# LTC1569.net
KiCad netlist of a schematic drawn in EasyEDA Pro
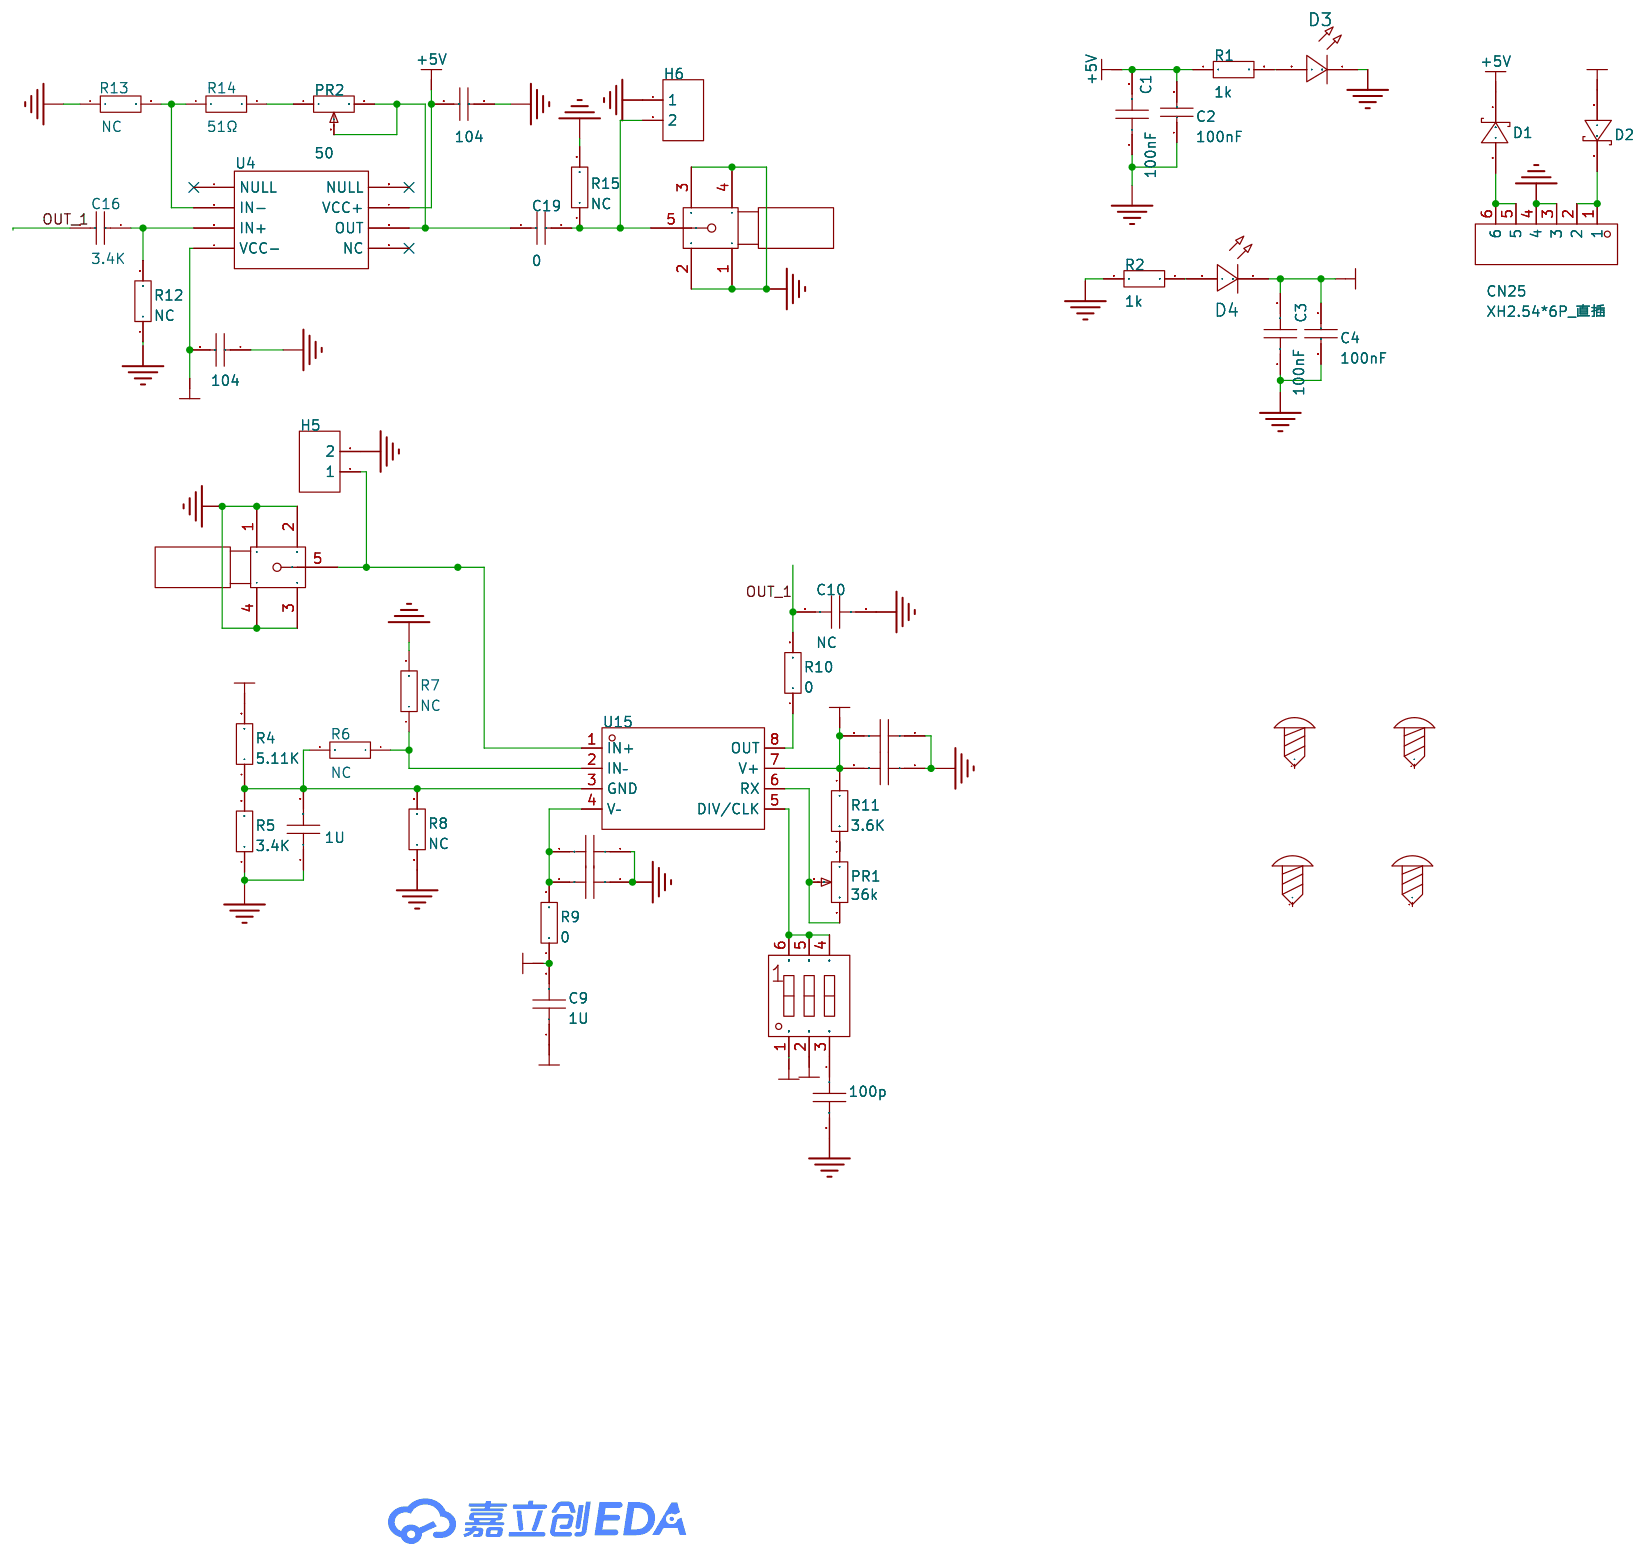
[diagram p0: schematic sheet]

(export (version "E")
  (design (tool "Eeschema 10.0.6"))
  (components
    (comp (ref "C1")
      (value "100nF")
      (footprint "easyedapro:C0805")
      (libsource (lib "easyedapro") (part "CapAcitance"))
    )
    (comp (ref "C2")
      (value "100nF")
      (footprint "easyedapro:C1210")
      (description "容值:10uF;精度:±10%;额定电压:25V;材质(温度系数):X7R;")
      (fields
        (field (name "Manufacturer Part") "CL32B106KAJNNNE")
        (field (name "Manufacturer") "SAMSUNG(三星)")
      )
      (libsource (lib "easyedapro") (part "CL32B106KAJNNNE"))
    )
    (comp (ref "C3")
      (value "100nF")
      (footprint "easyedapro:C0805")
      (libsource (lib "easyedapro") (part "CapAcitance"))
    )
    (comp (ref "C4")
      (value "100nF")
      (footprint "easyedapro:C1210")
      (description "容值:10uF;精度:±10%;额定电压:25V;材质(温度系数):X7R;")
      (fields
        (field (name "Manufacturer Part") "CL32B106KAJNNNE")
        (field (name "Manufacturer") "SAMSUNG(三星)")
      )
      (libsource (lib "easyedapro") (part "CL32B106KAJNNNE"))
    )
    (comp (ref "C6")
      (value "1U")
      (footprint "easyedapro:C0805")
      (libsource (lib "easyedapro") (part "CapAcitance"))
    )
    (comp (ref "C7")
      (value "100nF")
      (footprint "easyedapro:C0805")
      (libsource (lib "easyedapro") (part "CapAcitance"))
    )
    (comp (ref "C8")
      (value "100nF")
      (footprint "easyedapro:C0805")
      (libsource (lib "easyedapro") (part "CapAcitance"))
    )
    (comp (ref "C9")
      (value "1U")
      (footprint "easyedapro:C0805")
      (libsource (lib "easyedapro") (part "CapAcitance"))
    )
    (comp (ref "C10")
      (value "NC")
      (footprint "easyedapro:C0805")
      (libsource (lib "easyedapro") (part "CapAcitance"))
    )
    (comp (ref "C11")
      (value "100nF")
      (footprint "easyedapro:C0805")
      (libsource (lib "easyedapro") (part "CapAcitance"))
    )
    (comp (ref "C12")
      (value "100nF")
      (footprint "easyedapro:C0805")
      (libsource (lib "easyedapro") (part "CapAcitance"))
    )
    (comp (ref "C14")
      (value "100p")
      (footprint "easyedapro:C0805")
      (libsource (lib "easyedapro") (part "CapAcitance"))
    )
    (comp (ref "C16")
      (value "3.4K")
      (footprint "easyedapro:C0805")
      (description "容值:100pF;精度:±5%;额定电压:50V;材质(温度系数):C0G;")
      (fields
        (field (name "Manufacturer Part") "CL21C101JBANNNC")
        (field (name "Manufacturer") "SAMSUNG(三星)")
      )
      (libsource (lib "easyedapro") (part "CL21C101JBANNNC"))
    )
    (comp (ref "C17")
      (value "104")
      (footprint "easyedapro:C0805")
      (description "容值:100pF;精度:±5%;额定电压:50V;材质(温度系数):C0G;")
      (fields
        (field (name "Manufacturer Part") "CL21C101JBANNNC")
        (field (name "Manufacturer") "SAMSUNG(三星)")
      )
      (libsource (lib "easyedapro") (part "CL21C101JBANNNC"))
    )
    (comp (ref "C18")
      (value "104")
      (footprint "easyedapro:C0805")
      (description "容值:100pF;精度:±5%;额定电压:50V;材质(温度系数):C0G;")
      (fields
        (field (name "Manufacturer Part") "CL21C101JBANNNC")
        (field (name "Manufacturer") "SAMSUNG(三星)")
      )
      (libsource (lib "easyedapro") (part "CL21C101JBANNNC"))
    )
    (comp (ref "C19")
      (value "0")
      (footprint "easyedapro:C0805")
      (description "容值:100pF;精度:±5%;额定电压:50V;材质(温度系数):C0G;")
      (fields
        (field (name "Manufacturer Part") "CL21C101JBANNNC")
        (field (name "Manufacturer") "SAMSUNG(三星)")
      )
      (libsource (lib "easyedapro") (part "CL21C101JBANNNC"))
    )
    (comp (ref "CN25")
      (value "XH2.54*6P_直插")
      (footprint "easyedapro:CONN-TH_XH2.54-6P")
      (libsource (lib "easyedapro") (part "XH2.54*6P_直插"))
    )
    (comp (ref "D1")
      (value "SD103AWS")
      (footprint "easyedapro:SOD-323_L1.8-W1.3-LS2.5-RD")
      (description "正向压降(Vf):600mV@200mA;直流反向耐压(Vr):40V;整流电流:350mA;")
      (fields (field (name "Manufacturer") "Hottech(合科泰)"))
      (libsource (lib "easyedapro") (part "SD103AWS_C181207"))
    )
    (comp (ref "D2")
      (value "SD103AWS")
      (footprint "easyedapro:SOD-323_L1.8-W1.3-LS2.5-RD")
      (description "正向压降(Vf):600mV@200mA;直流反向耐压(Vr):40V;整流电流:350mA;")
      (fields (field (name "Manufacturer") "Hottech(合科泰)"))
      (libsource (lib "easyedapro") (part "SD103AWS_C181207"))
    )
    (comp (ref "D3")
      (value "~")
      (footprint "easyedapro:LED_0805")
      (libsource (lib "easyedapro") (part "LED_R"))
    )
    (comp (ref "D4")
      (value "~")
      (footprint "easyedapro:LED_0805")
      (libsource (lib "easyedapro") (part "LED_R"))
    )
    (comp (ref "H5")
      (value "~")
      (footprint "easyedapro:HDR-TH_2P-P2.54-V-F")
      (libsource (lib "easyedapro") (part "Header-Female-2.54_1x2"))
    )
    (comp (ref "H6")
      (value "~")
      (footprint "easyedapro:HDR-TH_2P-P2.54-V-F")
      (libsource (lib "easyedapro") (part "Header-Female-2.54_1x2"))
    )
    (comp (ref "PR1")
      (value "36k")
      (footprint "easyedapro:R_3296")
      (libsource (lib "easyedapro") (part "R_3296"))
    )
    (comp (ref "PR2")
      (value "50")
      (footprint "easyedapro:R_3296")
      (libsource (lib "easyedapro") (part "R_3296"))
    )
    (comp (ref "R1") (value "1k") (footprint "easyedapro:R0805") (libsource (lib "easyedapro") (part "电阻")))
    (comp (ref "R2") (value "1k") (footprint "easyedapro:R0805") (libsource (lib "easyedapro") (part "电阻")))
    (comp (ref "R4")
      (value "5.11K")
      (footprint "easyedapro:R0805")
      (libsource (lib "easyedapro") (part "电阻"))
    )
    (comp (ref "R5") (value "3.4K") (footprint "easyedapro:R0805") (libsource (lib "easyedapro") (part "电阻")))
    (comp (ref "R6") (value "NC") (footprint "easyedapro:R0805") (libsource (lib "easyedapro") (part "电阻")))
    (comp (ref "R7") (value "NC") (footprint "easyedapro:R0805") (libsource (lib "easyedapro") (part "电阻")))
    (comp (ref "R8") (value "NC") (footprint "easyedapro:R0805") (libsource (lib "easyedapro") (part "电阻")))
    (comp (ref "R9") (value "0") (footprint "easyedapro:R0805") (libsource (lib "easyedapro") (part "电阻")))
    (comp (ref "R10") (value "0") (footprint "easyedapro:R0805") (libsource (lib "easyedapro") (part "电阻")))
    (comp (ref "R11")
      (value "3.6K")
      (footprint "easyedapro:R0805")
      (libsource (lib "easyedapro") (part "电阻"))
    )
    (comp (ref "R12")
      (value "NC")
      (footprint "easyedapro:R0805")
      (description "电阻类型:厚膜电阻;阻值:51Ω;精度:±1%;功率:125mW;最大工作电压:150V;温度系数:±100ppm/°C;")
      (fields
        (field (name "Manufacturer Part") "0805W8F510JT5E")
        (field (name "Manufacturer") "UNI-ROYAL(厚声)")
      )
      (libsource (lib "easyedapro") (part "0805W8F510JT5E"))
    )
    (comp (ref "R13")
      (value "NC")
      (footprint "easyedapro:R0805")
      (description "电阻类型:厚膜电阻;阻值:51Ω;精度:±1%;功率:125mW;最大工作电压:150V;温度系数:±100ppm/°C;")
      (fields
        (field (name "Manufacturer Part") "0805W8F510JT5E")
        (field (name "Manufacturer") "UNI-ROYAL(厚声)")
      )
      (libsource (lib "easyedapro") (part "0805W8F510JT5E"))
    )
    (comp (ref "R14")
      (value "51Ω")
      (footprint "easyedapro:R0805")
      (description "电阻类型:厚膜电阻;阻值:511Ω;精度:±1%;功率:125mW;最大工作电压:150V;温度系数:±100ppm/°C;")
      (fields
        (field (name "Manufacturer Part") "0805W8F5110T5E")
        (field (name "Manufacturer") "UNI-ROYAL(厚声)")
      )
      (libsource (lib "easyedapro") (part "0805W8F5110T5E"))
    )
    (comp (ref "R15")
      (value "NC")
      (footprint "easyedapro:R0805")
      (description "电阻类型:厚膜电阻;阻值:51Ω;精度:±1%;功率:125mW;最大工作电压:150V;温度系数:±100ppm/°C;")
      (fields
        (field (name "Manufacturer Part") "0805W8F510JT5E")
        (field (name "Manufacturer") "UNI-ROYAL(厚声)")
      )
      (libsource (lib "easyedapro") (part "0805W8F510JT5E"))
    )
    (comp (ref "SCREW9")
      (value "~")
      (footprint "easyedapro:M3螺丝")
      (libsource (lib "easyedapro") (part "螺丝孔"))
    )
    (comp (ref "SCREW10")
      (value "~")
      (footprint "easyedapro:M3螺丝")
      (libsource (lib "easyedapro") (part "螺丝孔"))
    )
    (comp (ref "SCREW11")
      (value "~")
      (footprint "easyedapro:M3螺丝")
      (libsource (lib "easyedapro") (part "螺丝孔"))
    )
    (comp (ref "SCREW12")
      (value "~")
      (footprint "easyedapro:M3螺丝")
      (libsource (lib "easyedapro") (part "螺丝孔"))
    )
    (comp (ref "SW1")
      (value "DSIC03LS-P")
      (footprint "easyedapro:SW-SMD_6P-L8.6-W6.2-P2.54-LS9.8")
      (description "类型:平拨,凸起式;电路结构:单刀单掷;开关位数:3位;额定电流:25mA;额定电压:24V;使用寿命:3千次;颜色:黑色;")
      (fields (field (name "Manufacturer") "XKB Connectivity(中国星坤)"))
      (libsource (lib "easyedapro") (part "DSIC03LS-P"))
    )
    (comp (ref "U4")
      (value "~")
      (footprint "easyedapro:THS4001CD")
      (libsource (lib "easyedapro") (part "THS4001CD"))
    )
    (comp (ref "U15")
      (value "LTC1569IS8-6#TRPBF")
      (footprint "easyedapro:SO-8_L4.9-W3.9-P1.27-LS6.0-BL")
      (description "滤波器阶数:10;滤波器数:1;")
      (fields (field (name "Manufacturer") "ADI(亚德诺)"))
      (libsource (lib "easyedapro") (part "LTC1569IS8-6#TRPBF"))
    )
    (comp (ref "U16") (value "~") (footprint "easyedapro:SMA") (libsource (lib "easyedapro") (part "SMA")))
    (comp (ref "U17") (value "~") (footprint "easyedapro:SMA") (libsource (lib "easyedapro") (part "SMA")))
  )
  (nets
    (net (code "1") (name "+5V") (class "Default")
      (node (ref "C1") (pin "2") (pinfunction "2_2") (pintype "input"))
      (node (ref "C11") (pin "2") (pinfunction "2_2") (pintype "input"))
      (node (ref "C12") (pin "2") (pinfunction "2_2") (pintype "input"))
      (node (ref "C18") (pin "2") (pinfunction "2_2") (pintype "input"))
      (node (ref "C2") (pin "2") (pinfunction "2_2") (pintype "input"))
      (node (ref "C9") (pin "1") (pinfunction "1_1") (pintype "input"))
      (node (ref "D1") (pin "1") (pinfunction "C_1") (pintype "unspecified"))
      (node (ref "R1") (pin "1") (pinfunction "1_1") (pintype "input"))
      (node (ref "R11") (pin "1") (pinfunction "1_1") (pintype "input"))
      (node (ref "R4") (pin "2") (pinfunction "2_2") (pintype "input"))
      (node (ref "SW1") (pin "1") (pinfunction "PIN1_1") (pintype "unspecified"))
      (node (ref "U15") (pin "7") (pinfunction "V+_7") (pintype "unspecified"))
      (node (ref "U4") (pin "7") (pinfunction "VCC+_7") (pintype "input"))
    )
    (net (code "2") (name "-5V") (class "Default")
      (node (ref "C17") (pin "2") (pinfunction "2_2") (pintype "input"))
      (node (ref "C3") (pin "2") (pinfunction "2_2") (pintype "input"))
      (node (ref "C4") (pin "2") (pinfunction "2_2") (pintype "input"))
      (node (ref "C9") (pin "2") (pinfunction "2_2") (pintype "input"))
      (node (ref "D2") (pin "2") (pinfunction "A_2") (pintype "unspecified"))
      (node (ref "D4") (pin "1") (pinfunction "C_1") (pintype "input"))
      (node (ref "R9") (pin "1") (pinfunction "1_1") (pintype "input"))
      (node (ref "SW1") (pin "2") (pinfunction "PIN2_2") (pintype "unspecified"))
      (node (ref "U4") (pin "4") (pinfunction "VCC-_4") (pintype "input"))
    )
    (net (code "3") (name "/OUT_1") (class "Default")
      (node (ref "C10") (pin "2") (pinfunction "2_2") (pintype "input"))
      (node (ref "C16") (pin "1") (pinfunction "1_1") (pintype "input"))
      (node (ref "R10") (pin "2") (pinfunction "2_2") (pintype "input"))
    )
    (net (code "4") (name "GND") (class "Default")
      (node (ref "C1") (pin "1") (pinfunction "1_1") (pintype "input"))
      (node (ref "C10") (pin "1") (pinfunction "1_1") (pintype "input"))
      (node (ref "C11") (pin "1") (pinfunction "1_1") (pintype "input"))
      (node (ref "C12") (pin "1") (pinfunction "1_1") (pintype "input"))
      (node (ref "C14") (pin "2") (pinfunction "2_2") (pintype "input"))
      (node (ref "C17") (pin "1") (pinfunction "1_1") (pintype "input"))
      (node (ref "C18") (pin "1") (pinfunction "1_1") (pintype "input"))
      (node (ref "C2") (pin "1") (pinfunction "1_1") (pintype "input"))
      (node (ref "C3") (pin "1") (pinfunction "1_1") (pintype "input"))
      (node (ref "C4") (pin "1") (pinfunction "1_1") (pintype "input"))
      (node (ref "C6") (pin "1") (pinfunction "1_1") (pintype "input"))
      (node (ref "C7") (pin "1") (pinfunction "1_1") (pintype "input"))
      (node (ref "C8") (pin "1") (pinfunction "1_1") (pintype "input"))
      (node (ref "CN25") (pin "3") (pinfunction "3_3") (pintype "input"))
      (node (ref "CN25") (pin "4") (pinfunction "4_4") (pintype "input"))
      (node (ref "D3") (pin "1") (pinfunction "C_1") (pintype "input"))
      (node (ref "H5") (pin "2") (pinfunction "2_2") (pintype "input"))
      (node (ref "H6") (pin "1") (pinfunction "1_1") (pintype "input"))
      (node (ref "R12") (pin "1") (pinfunction "1_1") (pintype "input"))
      (node (ref "R13") (pin "1") (pinfunction "1_1") (pintype "input"))
      (node (ref "R15") (pin "2") (pinfunction "2_2") (pintype "input"))
      (node (ref "R2") (pin "1") (pinfunction "1_1") (pintype "input"))
      (node (ref "R5") (pin "1") (pinfunction "1_1") (pintype "input"))
      (node (ref "R7") (pin "2") (pinfunction "2_2") (pintype "input"))
      (node (ref "R8") (pin "1") (pinfunction "1_1") (pintype "input"))
      (node (ref "U16") (pin "1") (pinfunction "1_1") (pintype "input"))
      (node (ref "U16") (pin "2") (pinfunction "2_2") (pintype "input"))
      (node (ref "U16") (pin "3") (pinfunction "3_3") (pintype "input"))
      (node (ref "U16") (pin "4") (pinfunction "4_4") (pintype "input"))
      (node (ref "U17") (pin "1") (pinfunction "1_1") (pintype "input"))
      (node (ref "U17") (pin "2") (pinfunction "2_2") (pintype "input"))
      (node (ref "U17") (pin "3") (pinfunction "3_3") (pintype "input"))
      (node (ref "U17") (pin "4") (pinfunction "4_4") (pintype "input"))
    )
    (net (code "5") (name "Net-(C19-Pad2)") (class "Default")
      (node (ref "C19") (pin "2") (pinfunction "2_2") (pintype "input"))
      (node (ref "H6") (pin "2") (pinfunction "2_2") (pintype "input"))
      (node (ref "R15") (pin "1") (pinfunction "1_1") (pintype "input"))
      (node (ref "U17") (pin "5") (pinfunction "5_5") (pintype "input"))
    )
    (net (code "6") (name "Net-(D1-A)") (class "Default")
      (node (ref "CN25") (pin "5") (pinfunction "5_5") (pintype "input"))
      (node (ref "CN25") (pin "6") (pinfunction "6_6") (pintype "input"))
      (node (ref "D1") (pin "2") (pinfunction "A_2") (pintype "unspecified"))
    )
    (net (code "7") (name "Net-(D2-C)") (class "Default")
      (node (ref "CN25") (pin "1") (pinfunction "1_1") (pintype "input"))
      (node (ref "CN25") (pin "2") (pinfunction "2_2") (pintype "input"))
      (node (ref "D2") (pin "1") (pinfunction "C_1") (pintype "unspecified"))
    )
    (net (code "8") (name "Net-(D3-A)") (class "Default")
      (node (ref "D3") (pin "2") (pinfunction "A_2") (pintype "input"))
      (node (ref "R1") (pin "2") (pinfunction "2_2") (pintype "input"))
    )
    (net (code "9") (name "Net-(D4-A)") (class "Default")
      (node (ref "D4") (pin "2") (pinfunction "A_2") (pintype "input"))
      (node (ref "R2") (pin "2") (pinfunction "2_2") (pintype "input"))
    )
    (net (code "10") (name "Net-(PR1-Pad1)") (class "Default")
      (node (ref "PR1") (pin "1") (pinfunction "1_1") (pintype "input"))
      (node (ref "R11") (pin "2") (pinfunction "2_2") (pintype "input"))
    )
    (net (code "11") (name "Net-(PR2-Pad1)") (class "Default")
      (node (ref "PR2") (pin "1") (pinfunction "1_1") (pintype "input"))
      (node (ref "R14") (pin "2") (pinfunction "2_2") (pintype "input"))
    )
    (net (code "12") (name "Net-(SW1-PIN3)") (class "Default")
      (node (ref "C14") (pin "1") (pinfunction "1_1") (pintype "input"))
      (node (ref "SW1") (pin "3") (pinfunction "PIN3_3") (pintype "unspecified"))
    )
    (net (code "13") (name "Net-(SW1-PIN4)") (class "Default")
      (node (ref "SW1") (pin "4") (pinfunction "PIN4_4") (pintype "unspecified"))
      (node (ref "SW1") (pin "5") (pinfunction "PIN5_5") (pintype "unspecified"))
      (node (ref "SW1") (pin "6") (pinfunction "PIN6_6") (pintype "unspecified"))
      (node (ref "U15") (pin "5") (pinfunction "DIV/CLK_5") (pintype "unspecified"))
    )
    (net (code "14") (name "Net-(U4-IN+)") (class "Default")
      (node (ref "C16") (pin "2") (pinfunction "2_2") (pintype "input"))
      (node (ref "R12") (pin "2") (pinfunction "2_2") (pintype "input"))
      (node (ref "U4") (pin "3") (pinfunction "IN+_3") (pintype "input"))
    )
    (net (code "15") (name "Net-(U4-IN-)") (class "Default")
      (node (ref "R13") (pin "2") (pinfunction "2_2") (pintype "input"))
      (node (ref "R14") (pin "1") (pinfunction "1_1") (pintype "input"))
      (node (ref "U4") (pin "2") (pinfunction "IN-_2") (pintype "input"))
    )
    (net (code "16") (name "Net-(U4-OUT)") (class "Default")
      (node (ref "C19") (pin "1") (pinfunction "1_1") (pintype "input"))
      (node (ref "PR2") (pin "2") (pinfunction "2_2") (pintype "input"))
      (node (ref "PR2") (pin "3") (pinfunction "3_3") (pintype "input"))
      (node (ref "U4") (pin "6") (pinfunction "OUT_6") (pintype "input"))
    )
    (net (code "17") (name "Net-(U15-GND)") (class "Default")
      (node (ref "C6") (pin "2") (pinfunction "2_2") (pintype "input"))
      (node (ref "R4") (pin "1") (pinfunction "1_1") (pintype "input"))
      (node (ref "R5") (pin "2") (pinfunction "2_2") (pintype "input"))
      (node (ref "R6") (pin "2") (pinfunction "2_2") (pintype "input"))
      (node (ref "R8") (pin "2") (pinfunction "2_2") (pintype "input"))
      (node (ref "U15") (pin "3") (pinfunction "GND_3") (pintype "unspecified"))
    )
    (net (code "18") (name "Net-(U15-IN+)") (class "Default")
      (node (ref "H5") (pin "1") (pinfunction "1_1") (pintype "input"))
      (node (ref "U15") (pin "1") (pinfunction "IN+_1") (pintype "unspecified"))
      (node (ref "U16") (pin "5") (pinfunction "5_5") (pintype "input"))
    )
    (net (code "19") (name "Net-(U15-IN–)") (class "Default")
      (node (ref "R6") (pin "1") (pinfunction "1_1") (pintype "input"))
      (node (ref "R7") (pin "1") (pinfunction "1_1") (pintype "input"))
      (node (ref "U15") (pin "2") (pinfunction "IN–_2") (pintype "unspecified"))
    )
    (net (code "20") (name "Net-(U15-OUT)") (class "Default")
      (node (ref "R10") (pin "1") (pinfunction "1_1") (pintype "input"))
      (node (ref "U15") (pin "8") (pinfunction "OUT_8") (pintype "unspecified"))
    )
    (net (code "21") (name "Net-(U15-RX)") (class "Default")
      (node (ref "PR1") (pin "2") (pinfunction "2_2") (pintype "input"))
      (node (ref "PR1") (pin "3") (pinfunction "3_3") (pintype "input"))
      (node (ref "U15") (pin "6") (pinfunction "RX_6") (pintype "unspecified"))
    )
    (net (code "22") (name "Net-(U15-V–)") (class "Default")
      (node (ref "C7") (pin "2") (pinfunction "2_2") (pintype "input"))
      (node (ref "C8") (pin "2") (pinfunction "2_2") (pintype "input"))
      (node (ref "R9") (pin "2") (pinfunction "2_2") (pintype "input"))
      (node (ref "U15") (pin "4") (pinfunction "V–_4") (pintype "unspecified"))
    )
    (net (code "23") (name "unconnected-(SCREW9-Pad1)") (class "Default")
      (node (ref "SCREW9") (pin "1") (pinfunction "1_1") (pintype "input"))
    )
    (net (code "24") (name "unconnected-(SCREW10-Pad1)") (class "Default")
      (node (ref "SCREW10") (pin "1") (pinfunction "1_1") (pintype "input"))
    )
    (net (code "25") (name "unconnected-(SCREW11-Pad1)") (class "Default")
      (node (ref "SCREW11") (pin "1") (pinfunction "1_1") (pintype "input"))
    )
    (net (code "26") (name "unconnected-(SCREW12-Pad1)") (class "Default")
      (node (ref "SCREW12") (pin "1") (pinfunction "1_1") (pintype "input"))
    )
    (net (code "27") (name "unconnected-(U4-NC-Pad5)") (class "Default")
      (node (ref "U4") (pin "5") (pinfunction "NC_5") (pintype "input+no_connect"))
    )
    (net (code "28") (name "unconnected-(U4-NULL-Pad1)") (class "Default")
      (node (ref "U4") (pin "1") (pinfunction "NULL_1") (pintype "input+no_connect"))
    )
    (net (code "29") (name "unconnected-(U4-NULL-Pad8)") (class "Default")
      (node (ref "U4") (pin "8") (pinfunction "NULL_8") (pintype "input+no_connect"))
    )
  )
)
